# Dual_Power_Supply_design.net
KiCad netlist of a schematic drawn in EAGLE
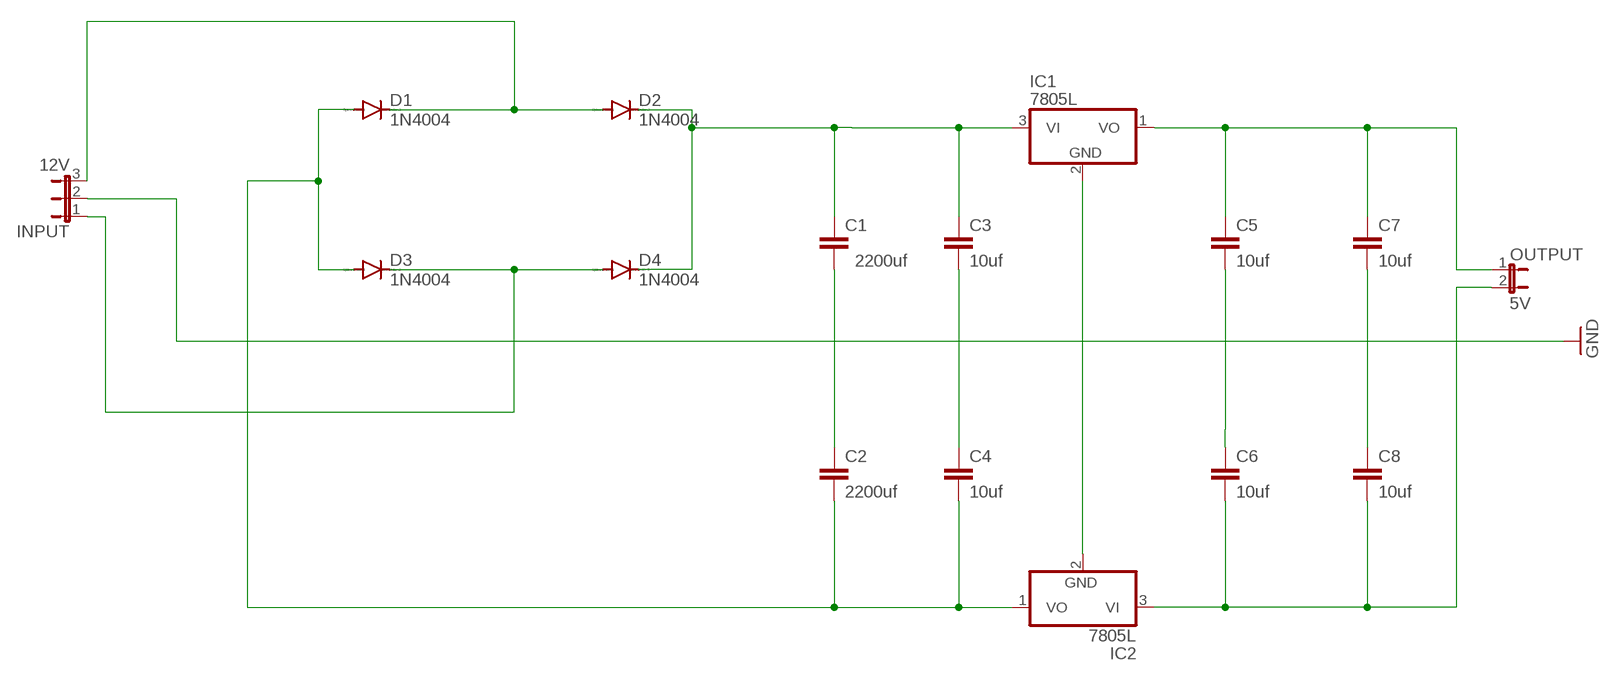
[diagram p0: schematic, sheet 1]

(export (version "E")
  (design (tool "Eeschema 10.0.6"))
  (components
    (comp (ref "C1")
      (value "2200uf")
      (footprint "eagle-import:C2.5-3")
      (libsource (lib "eagle-import") (part "C2,5-3"))
    )
    (comp (ref "C2")
      (value "2200uf")
      (footprint "eagle-import:C2.5-3")
      (libsource (lib "eagle-import") (part "C2,5-3"))
    )
    (comp (ref "C3")
      (value "10uf")
      (footprint "eagle-import:C2.5-3")
      (libsource (lib "eagle-import") (part "C2,5-3"))
    )
    (comp (ref "C4")
      (value "10uf")
      (footprint "eagle-import:C2.5-3")
      (libsource (lib "eagle-import") (part "C2,5-3"))
    )
    (comp (ref "C5")
      (value "10uf")
      (footprint "eagle-import:C2.5-3")
      (libsource (lib "eagle-import") (part "C2,5-3"))
    )
    (comp (ref "C6")
      (value "10uf")
      (footprint "eagle-import:C2.5-3")
      (libsource (lib "eagle-import") (part "C2,5-3"))
    )
    (comp (ref "C7")
      (value "10uf")
      (footprint "eagle-import:C2.5-3")
      (libsource (lib "eagle-import") (part "C2,5-3"))
    )
    (comp (ref "C8")
      (value "10uf")
      (footprint "eagle-import:C2.5-3")
      (libsource (lib "eagle-import") (part "C2,5-3"))
    )
    (comp (ref "D1")
      (value "1N4004")
      (footprint "eagle-import:DO41-10")
      (libsource (lib "eagle-import") (part "1N4004"))
    )
    (comp (ref "D2")
      (value "1N4004")
      (footprint "eagle-import:DO41-10")
      (libsource (lib "eagle-import") (part "1N4004"))
    )
    (comp (ref "D3")
      (value "1N4004")
      (footprint "eagle-import:DO41-10")
      (libsource (lib "eagle-import") (part "1N4004"))
    )
    (comp (ref "D4")
      (value "1N4004")
      (footprint "eagle-import:DO41-10")
      (libsource (lib "eagle-import") (part "1N4004"))
    )
    (comp (ref "IC1")
      (value "7805L")
      (footprint "eagle-import:TO92")
      (libsource (lib "eagle-import") (part "78L05"))
    )
    (comp (ref "IC2")
      (value "7805L")
      (footprint "eagle-import:TO92")
      (libsource (lib "eagle-import") (part "78L05"))
    )
    (comp (ref "INPUT")
      (value "12V")
      (footprint "eagle-import:JP2")
      (libsource (lib "eagle-import") (part "JP2E"))
    )
    (comp (ref "OUTPUT")
      (value "5V")
      (footprint "eagle-import:JP1")
      (libsource (lib "eagle-import") (part "JP1E"))
    )
  )
  (nets
    (net (code "1") (name "GND") (class "Default")
      (node (ref "INPUT") (pin "2") (pinfunction "2_2") (pintype "passive"))
    )
    (net (code "2") (name "Net-(C1-Pad2)") (class "Default")
      (node (ref "C1") (pin "2") (pinfunction "2_2") (pintype "passive"))
      (node (ref "C2") (pin "1") (pinfunction "1_1") (pintype "passive"))
    )
    (net (code "3") (name "Net-(C3-Pad2)") (class "Default")
      (node (ref "C3") (pin "2") (pinfunction "2_2") (pintype "passive"))
      (node (ref "C4") (pin "1") (pinfunction "1_1") (pintype "passive"))
    )
    (net (code "4") (name "Net-(C5-Pad2)") (class "Default")
      (node (ref "C5") (pin "2") (pinfunction "2_2") (pintype "passive"))
      (node (ref "C6") (pin "1") (pinfunction "1_1") (pintype "passive"))
    )
    (net (code "5") (name "Net-(C7-Pad2)") (class "Default")
      (node (ref "C7") (pin "2") (pinfunction "2_2") (pintype "passive"))
      (node (ref "C8") (pin "1") (pinfunction "1_1") (pintype "passive"))
    )
    (net (code "6") (name "Net-(D1-PadC)") (class "Default")
      (node (ref "D1") (pin "C") (pinfunction "C_C") (pintype "passive"))
      (node (ref "D2") (pin "A") (pinfunction "A_A") (pintype "passive"))
      (node (ref "INPUT") (pin "3") (pinfunction "3_3") (pintype "passive"))
    )
    (net (code "7") (name "Net-(D3-PadC)") (class "Default")
      (node (ref "D3") (pin "C") (pinfunction "C_C") (pintype "passive"))
      (node (ref "D4") (pin "A") (pinfunction "A_A") (pintype "passive"))
      (node (ref "INPUT") (pin "1") (pinfunction "1_1") (pintype "passive"))
    )
    (net (code "8") (name "Net-(IC1-GND)") (class "Default")
      (node (ref "IC1") (pin "2") (pinfunction "GND_2") (pintype "passive"))
      (node (ref "IC2") (pin "2") (pinfunction "GND_2") (pintype "passive"))
    )
    (net (code "9") (name "Net-(IC1-VI)") (class "Default")
      (node (ref "C1") (pin "1") (pinfunction "1_1") (pintype "passive"))
      (node (ref "C3") (pin "1") (pinfunction "1_1") (pintype "passive"))
      (node (ref "D2") (pin "C") (pinfunction "C_C") (pintype "passive"))
      (node (ref "D4") (pin "C") (pinfunction "C_C") (pintype "passive"))
      (node (ref "IC1") (pin "3") (pinfunction "VI_3") (pintype "input"))
    )
    (net (code "10") (name "Net-(IC1-VO)") (class "Default")
      (node (ref "C5") (pin "1") (pinfunction "1_1") (pintype "passive"))
      (node (ref "C7") (pin "1") (pinfunction "1_1") (pintype "passive"))
      (node (ref "IC1") (pin "1") (pinfunction "VO_1") (pintype "passive"))
      (node (ref "OUTPUT") (pin "1") (pinfunction "1_1") (pintype "passive"))
    )
    (net (code "11") (name "Net-(IC2-VI)") (class "Default")
      (node (ref "C6") (pin "2") (pinfunction "2_2") (pintype "passive"))
      (node (ref "C8") (pin "2") (pinfunction "2_2") (pintype "passive"))
      (node (ref "IC2") (pin "3") (pinfunction "VI_3") (pintype "input"))
      (node (ref "OUTPUT") (pin "2") (pinfunction "2_2") (pintype "passive"))
    )
    (net (code "12") (name "Net-(IC2-VO)") (class "Default")
      (node (ref "C2") (pin "2") (pinfunction "2_2") (pintype "passive"))
      (node (ref "C4") (pin "2") (pinfunction "2_2") (pintype "passive"))
      (node (ref "D1") (pin "A") (pinfunction "A_A") (pintype "passive"))
      (node (ref "D3") (pin "A") (pinfunction "A_A") (pintype "passive"))
      (node (ref "IC2") (pin "1") (pinfunction "VO_1") (pintype "passive"))
    )
  )
)
